# Hub.net
KiCad netlist of a schematic drawn in EAGLE
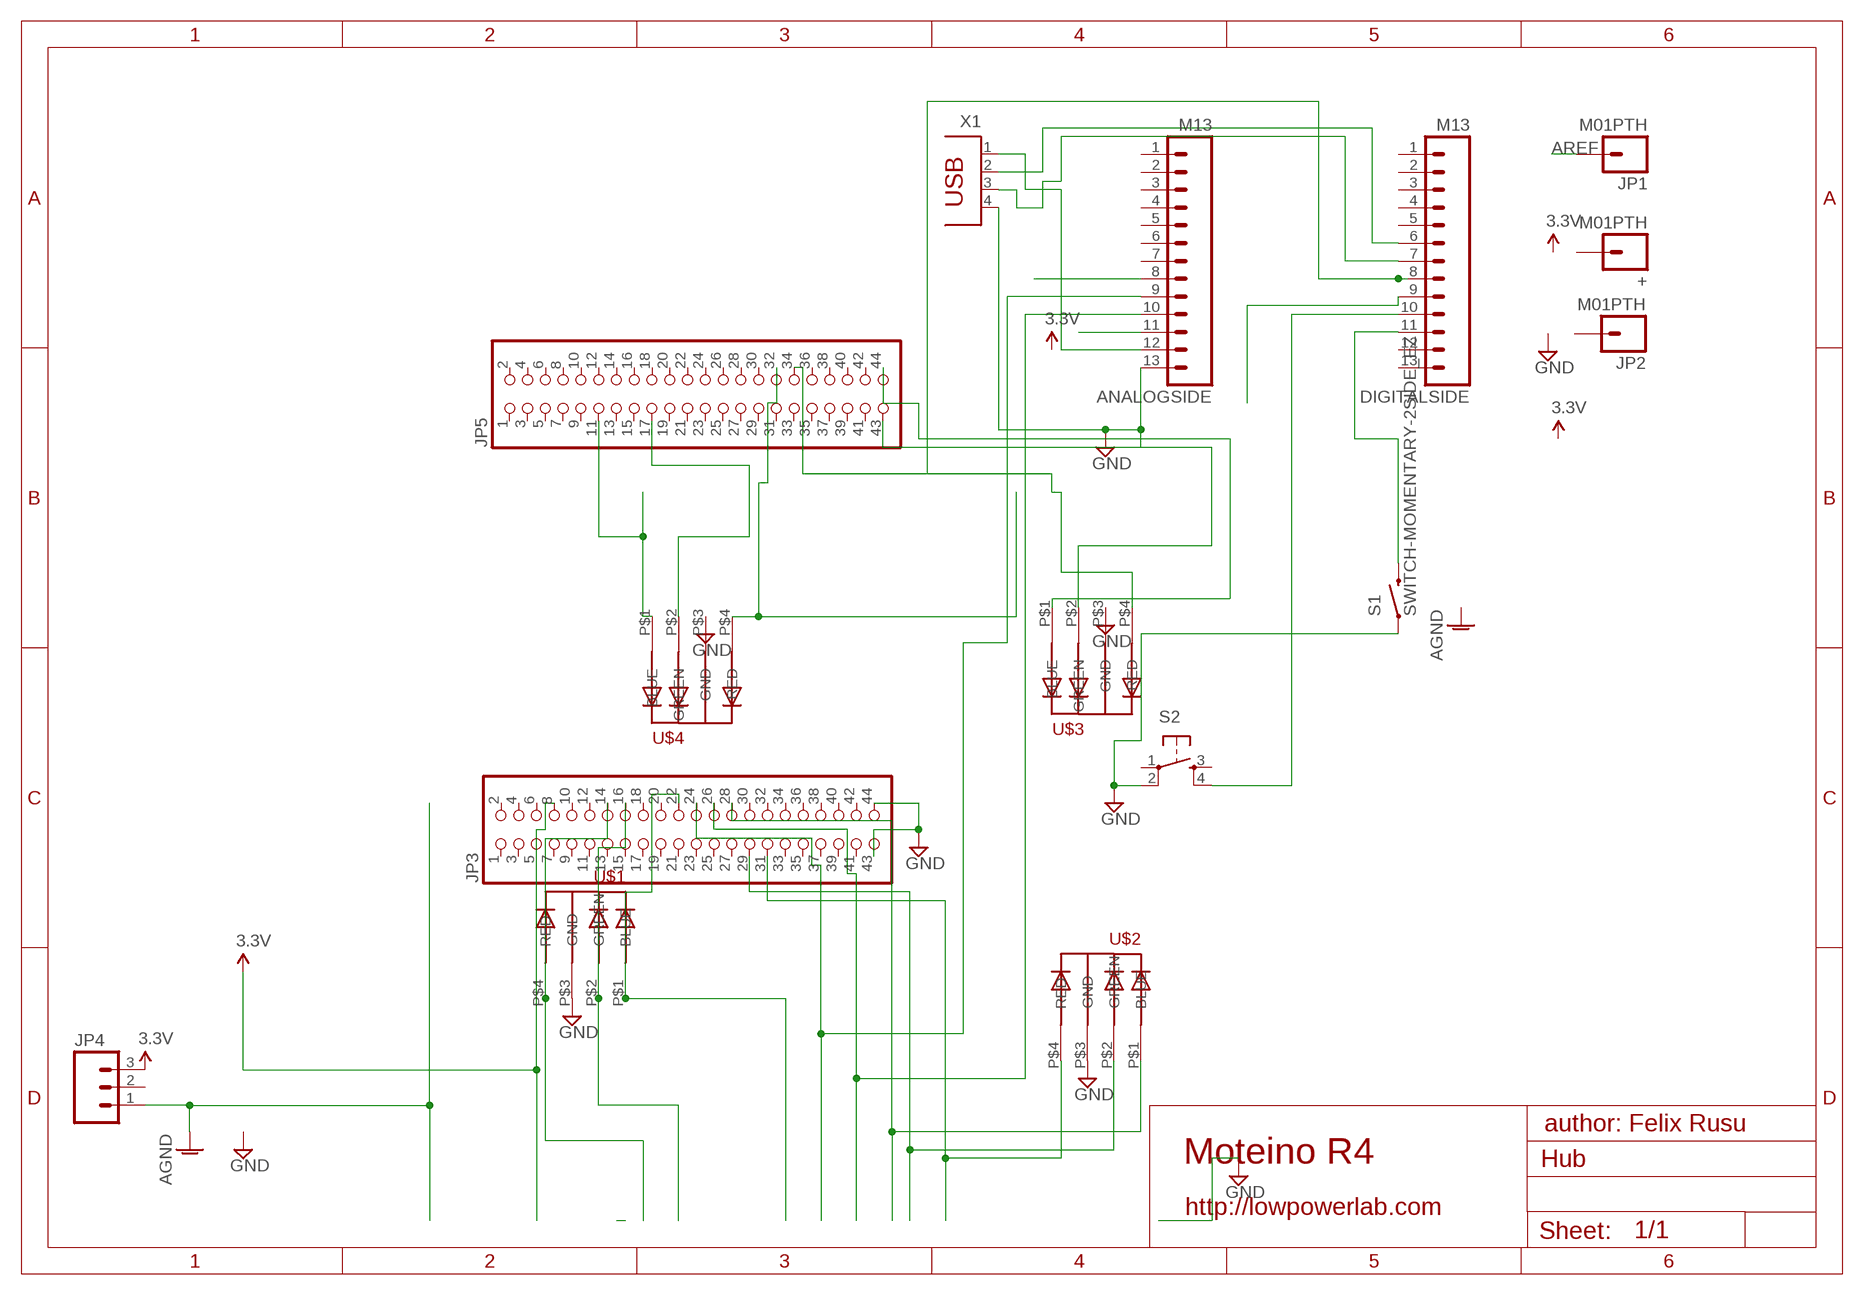
[diagram p0: schematic, sheet 1]

(export (version "E")
  (design (tool "Eeschema 10.0.6"))
  (components
    (comp (ref "+")
      (value "M01PTH")
      (footprint "eagle-import:1X01")
      (libsource (lib "eagle-import") (part "M01PTH"))
    )
    (comp (ref "ANALOGSIDE")
      (value "M13")
      (footprint "eagle-import:1X13")
      (libsource (lib "eagle-import") (part "M13"))
    )
    (comp (ref "DIGITALSIDE")
      (value "M13")
      (footprint "eagle-import:1X13")
      (libsource (lib "eagle-import") (part "M13"))
    )
    (comp (ref "JP1")
      (value "M01PTH")
      (footprint "eagle-import:1X01")
      (libsource (lib "eagle-import") (part "M01PTH"))
    )
    (comp (ref "JP2")
      (value "M01PTH")
      (footprint "eagle-import:1X01")
      (libsource (lib "eagle-import") (part "M01PTH"))
    )
    (comp (ref "JP3")
      (value "PINHD-2X22")
      (footprint "eagle-import:2X22")
      (libsource (lib "eagle-import") (part "PINHD-2X22"))
    )
    (comp (ref "JP4")
      (value "M03PTH")
      (footprint "eagle-import:1X03")
      (libsource (lib "eagle-import") (part "M03PTH"))
    )
    (comp (ref "JP5")
      (value "PINHD-2X22")
      (footprint "eagle-import:2X22")
      (libsource (lib "eagle-import") (part "PINHD-2X22"))
    )
    (comp (ref "S1")
      (value "SWITCH-MOMENTARY-2SIDE_EZ")
      (footprint "eagle-import:TACTILE-PTH-SIDEEZ")
      (libsource (lib "eagle-import") (part "SWITCH-MOMENTARY-2SIDE_EZ"))
    )
    (comp (ref "S2")
      (value "TAC_SWITCHPTH")
      (footprint "eagle-import:TACTILE-PTH")
      (libsource (lib "eagle-import") (part "TAC_SWITCHPTH"))
    )
    (comp (ref "U$1")
      (value "5MMRGBLED")
      (footprint "eagle-import:LED5MMRGB")
      (libsource (lib "eagle-import") (part "5MMRGBLED"))
    )
    (comp (ref "U$2")
      (value "5MMRGBLED")
      (footprint "eagle-import:LED5MMRGB")
      (libsource (lib "eagle-import") (part "5MMRGBLED"))
    )
    (comp (ref "U$3")
      (value "5MMRGBLED")
      (footprint "eagle-import:LED5MMRGB")
      (libsource (lib "eagle-import") (part "5MMRGBLED"))
    )
    (comp (ref "U$4")
      (value "5MMRGBLED")
      (footprint "eagle-import:LED5MMRGB")
      (libsource (lib "eagle-import") (part "5MMRGBLED"))
    )
    (comp (ref "X1")
      (value "PN87520")
      (footprint "eagle-import:PN87520")
      (libsource (lib "eagle-import") (part "PN87520"))
    )
  )
  (nets
    (net (code "1") (name "/AREF") (class "Default")
      (node (ref "JP1") (pin "1") (pinfunction "1_1") (pintype "passive"))
    )
    (net (code "2") (name "3.3V") (class "Default")
      (node (ref "JP3") (pin "8") (pinfunction "8_8") (pintype "passive"))
      (node (ref "JP4") (pin "3") (pinfunction "3_3") (pintype "passive"))
    )
    (net (code "3") (name "AGND") (class "Default")
      (node (ref "JP4") (pin "1") (pinfunction "1_1") (pintype "passive"))
    )
    (net (code "4") (name "GND") (class "Default")
      (node (ref "ANALOGSIDE") (pin "13") (pinfunction "13_13") (pintype "passive"))
      (node (ref "JP3") (pin "43") (pinfunction "43_43") (pintype "passive"))
      (node (ref "JP3") (pin "44") (pinfunction "44_44") (pintype "passive"))
      (node (ref "S1") (pin "1") (pinfunction "1_1") (pintype "passive"))
      (node (ref "S2") (pin "2") (pinfunction "2_2") (pintype "passive"))
      (node (ref "U$1") (pin "P$3") (pinfunction "GND_P$3") (pintype "bidirectional"))
      (node (ref "U$2") (pin "P$3") (pinfunction "GND_P$3") (pintype "bidirectional"))
      (node (ref "U$3") (pin "P$3") (pinfunction "GND_P$3") (pintype "bidirectional"))
      (node (ref "U$4") (pin "P$3") (pinfunction "GND_P$3") (pintype "bidirectional"))
      (node (ref "X1") (pin "4") (pinfunction "4_4") (pintype "passive"))
    )
    (net (code "5") (name "Net-(ANALOGSIDE-Pad9)") (class "Default")
      (node (ref "ANALOGSIDE") (pin "9") (pinfunction "9_9") (pintype "passive"))
      (node (ref "JP3") (pin "24") (pinfunction "24_24") (pintype "passive"))
    )
    (net (code "6") (name "Net-(ANALOGSIDE-Pad10)") (class "Default")
      (node (ref "ANALOGSIDE") (pin "10") (pinfunction "10_10") (pintype "passive"))
      (node (ref "JP3") (pin "26") (pinfunction "26_26") (pintype "passive"))
    )
    (net (code "7") (name "Net-(ANALOGSIDE-Pad12)") (class "Default")
      (node (ref "ANALOGSIDE") (pin "12") (pinfunction "12_12") (pintype "passive"))
      (node (ref "X1") (pin "1") (pinfunction "1_1") (pintype "passive"))
    )
    (net (code "8") (name "Net-(DIGITALSIDE-Pad6)") (class "Default")
      (node (ref "DIGITALSIDE") (pin "6") (pinfunction "6_6") (pintype "passive"))
      (node (ref "X1") (pin "2") (pinfunction "2_2") (pintype "passive"))
    )
    (net (code "9") (name "Net-(DIGITALSIDE-Pad7)") (class "Default")
      (node (ref "DIGITALSIDE") (pin "7") (pinfunction "7_7") (pintype "passive"))
      (node (ref "X1") (pin "3") (pinfunction "3_3") (pintype "passive"))
    )
    (net (code "10") (name "Net-(DIGITALSIDE-Pad10)") (class "Default")
      (node (ref "DIGITALSIDE") (pin "10") (pinfunction "10_10") (pintype "passive"))
      (node (ref "S2") (pin "4") (pinfunction "4_4") (pintype "passive"))
    )
    (net (code "11") (name "Net-(DIGITALSIDE-Pad11)") (class "Default")
      (node (ref "DIGITALSIDE") (pin "11") (pinfunction "11_11") (pintype "passive"))
      (node (ref "S1") (pin "2") (pinfunction "2_2") (pintype "passive"))
    )
    (net (code "12") (name "Net-(U$1-BLUE)") (class "Default")
      (node (ref "JP3") (pin "22") (pinfunction "22_22") (pintype "passive"))
      (node (ref "U$1") (pin "P$1") (pinfunction "BLUE_P$1") (pintype "bidirectional"))
    )
    (net (code "13") (name "Net-(U$1-GREEN)") (class "Default")
      (node (ref "JP3") (pin "16") (pinfunction "16_16") (pintype "passive"))
      (node (ref "U$1") (pin "P$2") (pinfunction "GREEN_P$2") (pintype "bidirectional"))
    )
    (net (code "14") (name "Net-(U$1-RED)") (class "Default")
      (node (ref "JP3") (pin "14") (pinfunction "14_14") (pintype "passive"))
      (node (ref "U$1") (pin "P$4") (pinfunction "RED_P$4") (pintype "bidirectional"))
    )
    (net (code "15") (name "Net-(U$2-BLUE)") (class "Default")
      (node (ref "JP3") (pin "28") (pinfunction "28_28") (pintype "passive"))
      (node (ref "U$2") (pin "P$1") (pinfunction "BLUE_P$1") (pintype "bidirectional"))
    )
    (net (code "16") (name "Net-(U$2-GREEN)") (class "Default")
      (node (ref "JP3") (pin "29") (pinfunction "29_29") (pintype "passive"))
      (node (ref "U$2") (pin "P$2") (pinfunction "GREEN_P$2") (pintype "bidirectional"))
    )
    (net (code "17") (name "Net-(U$2-RED)") (class "Default")
      (node (ref "JP3") (pin "31") (pinfunction "31_31") (pintype "passive"))
      (node (ref "U$2") (pin "P$4") (pinfunction "RED_P$4") (pintype "bidirectional"))
    )
    (net (code "18") (name "Net-(U$3-BLUE)") (class "Default")
      (node (ref "JP5") (pin "44") (pinfunction "44_44") (pintype "passive"))
      (node (ref "U$3") (pin "P$1") (pinfunction "BLUE_P$1") (pintype "bidirectional"))
    )
    (net (code "19") (name "Net-(U$3-GREEN)") (class "Default")
      (node (ref "JP5") (pin "43") (pinfunction "43_43") (pintype "passive"))
      (node (ref "U$3") (pin "P$2") (pinfunction "GREEN_P$2") (pintype "bidirectional"))
    )
    (net (code "20") (name "Net-(U$3-RED)") (class "Default")
      (node (ref "JP5") (pin "34") (pinfunction "34_34") (pintype "passive"))
      (node (ref "U$3") (pin "P$4") (pinfunction "RED_P$4") (pintype "bidirectional"))
    )
    (net (code "21") (name "Net-(U$4-BLUE)") (class "Default")
      (node (ref "JP5") (pin "11") (pinfunction "11_11") (pintype "passive"))
      (node (ref "U$4") (pin "P$1") (pinfunction "BLUE_P$1") (pintype "bidirectional"))
    )
    (net (code "22") (name "Net-(U$4-GREEN)") (class "Default")
      (node (ref "JP5") (pin "17") (pinfunction "17_17") (pintype "passive"))
      (node (ref "U$4") (pin "P$2") (pinfunction "GREEN_P$2") (pintype "bidirectional"))
    )
    (net (code "23") (name "Net-(U$4-RED)") (class "Default")
      (node (ref "JP5") (pin "32") (pinfunction "32_32") (pintype "passive"))
      (node (ref "U$4") (pin "P$4") (pinfunction "RED_P$4") (pintype "bidirectional"))
    )
    (net (code "24") (name "unconnected-(+-Pad1)") (class "Default")
      (node (ref "+") (pin "1") (pinfunction "1_1") (pintype "passive"))
    )
    (net (code "25") (name "unconnected-(ANALOGSIDE-Pad1)") (class "Default")
      (node (ref "ANALOGSIDE") (pin "1") (pinfunction "1_1") (pintype "passive"))
    )
    (net (code "26") (name "unconnected-(ANALOGSIDE-Pad2)") (class "Default")
      (node (ref "ANALOGSIDE") (pin "2") (pinfunction "2_2") (pintype "passive"))
    )
    (net (code "27") (name "unconnected-(ANALOGSIDE-Pad3)") (class "Default")
      (node (ref "ANALOGSIDE") (pin "3") (pinfunction "3_3") (pintype "passive"))
    )
    (net (code "28") (name "unconnected-(ANALOGSIDE-Pad4)") (class "Default")
      (node (ref "ANALOGSIDE") (pin "4") (pinfunction "4_4") (pintype "passive"))
    )
    (net (code "29") (name "unconnected-(ANALOGSIDE-Pad5)") (class "Default")
      (node (ref "ANALOGSIDE") (pin "5") (pinfunction "5_5") (pintype "passive"))
    )
    (net (code "30") (name "unconnected-(ANALOGSIDE-Pad6)") (class "Default")
      (node (ref "ANALOGSIDE") (pin "6") (pinfunction "6_6") (pintype "passive"))
    )
    (net (code "31") (name "unconnected-(ANALOGSIDE-Pad7)") (class "Default")
      (node (ref "ANALOGSIDE") (pin "7") (pinfunction "7_7") (pintype "passive"))
    )
    (net (code "32") (name "unconnected-(ANALOGSIDE-Pad8)") (class "Default")
      (node (ref "ANALOGSIDE") (pin "8") (pinfunction "8_8") (pintype "passive"))
    )
    (net (code "33") (name "unconnected-(ANALOGSIDE-Pad11)") (class "Default")
      (node (ref "ANALOGSIDE") (pin "11") (pinfunction "11_11") (pintype "passive"))
    )
    (net (code "34") (name "unconnected-(DIGITALSIDE-Pad1)") (class "Default")
      (node (ref "DIGITALSIDE") (pin "1") (pinfunction "1_1") (pintype "passive"))
    )
    (net (code "35") (name "unconnected-(DIGITALSIDE-Pad2)") (class "Default")
      (node (ref "DIGITALSIDE") (pin "2") (pinfunction "2_2") (pintype "passive"))
    )
    (net (code "36") (name "unconnected-(DIGITALSIDE-Pad3)") (class "Default")
      (node (ref "DIGITALSIDE") (pin "3") (pinfunction "3_3") (pintype "passive"))
    )
    (net (code "37") (name "unconnected-(DIGITALSIDE-Pad4)") (class "Default")
      (node (ref "DIGITALSIDE") (pin "4") (pinfunction "4_4") (pintype "passive"))
    )
    (net (code "38") (name "unconnected-(DIGITALSIDE-Pad5)") (class "Default")
      (node (ref "DIGITALSIDE") (pin "5") (pinfunction "5_5") (pintype "passive"))
    )
    (net (code "39") (name "unconnected-(DIGITALSIDE-Pad8)") (class "Default")
      (node (ref "DIGITALSIDE") (pin "8") (pinfunction "8_8") (pintype "passive"))
    )
    (net (code "40") (name "unconnected-(DIGITALSIDE-Pad9)") (class "Default")
      (node (ref "DIGITALSIDE") (pin "9") (pinfunction "9_9") (pintype "passive"))
    )
    (net (code "41") (name "unconnected-(DIGITALSIDE-Pad12)") (class "Default")
      (node (ref "DIGITALSIDE") (pin "12") (pinfunction "12_12") (pintype "passive"))
    )
    (net (code "42") (name "unconnected-(DIGITALSIDE-Pad13)") (class "Default")
      (node (ref "DIGITALSIDE") (pin "13") (pinfunction "13_13") (pintype "passive"))
    )
    (net (code "43") (name "unconnected-(JP2-Pad1)") (class "Default")
      (node (ref "JP2") (pin "1") (pinfunction "1_1") (pintype "passive"))
    )
    (net (code "44") (name "unconnected-(JP3-Pad1)") (class "Default")
      (node (ref "JP3") (pin "1") (pinfunction "1_1") (pintype "passive"))
    )
    (net (code "45") (name "unconnected-(JP3-Pad2)") (class "Default")
      (node (ref "JP3") (pin "2") (pinfunction "2_2") (pintype "passive"))
    )
    (net (code "46") (name "unconnected-(JP3-Pad3)") (class "Default")
      (node (ref "JP3") (pin "3") (pinfunction "3_3") (pintype "passive"))
    )
    (net (code "47") (name "unconnected-(JP3-Pad4)") (class "Default")
      (node (ref "JP3") (pin "4") (pinfunction "4_4") (pintype "passive"))
    )
    (net (code "48") (name "unconnected-(JP3-Pad5)") (class "Default")
      (node (ref "JP3") (pin "5") (pinfunction "5_5") (pintype "passive"))
    )
    (net (code "49") (name "unconnected-(JP3-Pad6)") (class "Default")
      (node (ref "JP3") (pin "6") (pinfunction "6_6") (pintype "passive"))
    )
    (net (code "50") (name "unconnected-(JP3-Pad7)") (class "Default")
      (node (ref "JP3") (pin "7") (pinfunction "7_7") (pintype "passive"))
    )
    (net (code "51") (name "unconnected-(JP3-Pad9)") (class "Default")
      (node (ref "JP3") (pin "9") (pinfunction "9_9") (pintype "passive"))
    )
    (net (code "52") (name "unconnected-(JP3-Pad10)") (class "Default")
      (node (ref "JP3") (pin "10") (pinfunction "10_10") (pintype "passive"))
    )
    (net (code "53") (name "unconnected-(JP3-Pad11)") (class "Default")
      (node (ref "JP3") (pin "11") (pinfunction "11_11") (pintype "passive"))
    )
    (net (code "54") (name "unconnected-(JP3-Pad12)") (class "Default")
      (node (ref "JP3") (pin "12") (pinfunction "12_12") (pintype "passive"))
    )
    (net (code "55") (name "unconnected-(JP3-Pad13)") (class "Default")
      (node (ref "JP3") (pin "13") (pinfunction "13_13") (pintype "passive"))
    )
    (net (code "56") (name "unconnected-(JP3-Pad15)") (class "Default")
      (node (ref "JP3") (pin "15") (pinfunction "15_15") (pintype "passive"))
    )
    (net (code "57") (name "unconnected-(JP3-Pad17)") (class "Default")
      (node (ref "JP3") (pin "17") (pinfunction "17_17") (pintype "passive"))
    )
    (net (code "58") (name "unconnected-(JP3-Pad18)") (class "Default")
      (node (ref "JP3") (pin "18") (pinfunction "18_18") (pintype "passive"))
    )
    (net (code "59") (name "unconnected-(JP3-Pad19)") (class "Default")
      (node (ref "JP3") (pin "19") (pinfunction "19_19") (pintype "passive"))
    )
    (net (code "60") (name "unconnected-(JP3-Pad20)") (class "Default")
      (node (ref "JP3") (pin "20") (pinfunction "20_20") (pintype "passive"))
    )
    (net (code "61") (name "unconnected-(JP3-Pad21)") (class "Default")
      (node (ref "JP3") (pin "21") (pinfunction "21_21") (pintype "passive"))
    )
    (net (code "62") (name "unconnected-(JP3-Pad23)") (class "Default")
      (node (ref "JP3") (pin "23") (pinfunction "23_23") (pintype "passive"))
    )
    (net (code "63") (name "unconnected-(JP3-Pad25)") (class "Default")
      (node (ref "JP3") (pin "25") (pinfunction "25_25") (pintype "passive"))
    )
    (net (code "64") (name "unconnected-(JP3-Pad27)") (class "Default")
      (node (ref "JP3") (pin "27") (pinfunction "27_27") (pintype "passive"))
    )
    (net (code "65") (name "unconnected-(JP3-Pad30)") (class "Default")
      (node (ref "JP3") (pin "30") (pinfunction "30_30") (pintype "passive"))
    )
    (net (code "66") (name "unconnected-(JP3-Pad32)") (class "Default")
      (node (ref "JP3") (pin "32") (pinfunction "32_32") (pintype "passive"))
    )
    (net (code "67") (name "unconnected-(JP3-Pad33)") (class "Default")
      (node (ref "JP3") (pin "33") (pinfunction "33_33") (pintype "passive"))
    )
    (net (code "68") (name "unconnected-(JP3-Pad34)") (class "Default")
      (node (ref "JP3") (pin "34") (pinfunction "34_34") (pintype "passive"))
    )
    (net (code "69") (name "unconnected-(JP3-Pad35)") (class "Default")
      (node (ref "JP3") (pin "35") (pinfunction "35_35") (pintype "passive"))
    )
    (net (code "70") (name "unconnected-(JP3-Pad36)") (class "Default")
      (node (ref "JP3") (pin "36") (pinfunction "36_36") (pintype "passive"))
    )
    (net (code "71") (name "unconnected-(JP3-Pad37)") (class "Default")
      (node (ref "JP3") (pin "37") (pinfunction "37_37") (pintype "passive"))
    )
    (net (code "72") (name "unconnected-(JP3-Pad38)") (class "Default")
      (node (ref "JP3") (pin "38") (pinfunction "38_38") (pintype "passive"))
    )
    (net (code "73") (name "unconnected-(JP3-Pad39)") (class "Default")
      (node (ref "JP3") (pin "39") (pinfunction "39_39") (pintype "passive"))
    )
    (net (code "74") (name "unconnected-(JP3-Pad40)") (class "Default")
      (node (ref "JP3") (pin "40") (pinfunction "40_40") (pintype "passive"))
    )
    (net (code "75") (name "unconnected-(JP3-Pad41)") (class "Default")
      (node (ref "JP3") (pin "41") (pinfunction "41_41") (pintype "passive"))
    )
    (net (code "76") (name "unconnected-(JP3-Pad42)") (class "Default")
      (node (ref "JP3") (pin "42") (pinfunction "42_42") (pintype "passive"))
    )
    (net (code "77") (name "unconnected-(JP4-Pad2)") (class "Default")
      (node (ref "JP4") (pin "2") (pinfunction "2_2") (pintype "passive"))
    )
    (net (code "78") (name "unconnected-(JP5-Pad1)") (class "Default")
      (node (ref "JP5") (pin "1") (pinfunction "1_1") (pintype "passive"))
    )
    (net (code "79") (name "unconnected-(JP5-Pad2)") (class "Default")
      (node (ref "JP5") (pin "2") (pinfunction "2_2") (pintype "passive"))
    )
    (net (code "80") (name "unconnected-(JP5-Pad3)") (class "Default")
      (node (ref "JP5") (pin "3") (pinfunction "3_3") (pintype "passive"))
    )
    (net (code "81") (name "unconnected-(JP5-Pad4)") (class "Default")
      (node (ref "JP5") (pin "4") (pinfunction "4_4") (pintype "passive"))
    )
    (net (code "82") (name "unconnected-(JP5-Pad5)") (class "Default")
      (node (ref "JP5") (pin "5") (pinfunction "5_5") (pintype "passive"))
    )
    (net (code "83") (name "unconnected-(JP5-Pad6)") (class "Default")
      (node (ref "JP5") (pin "6") (pinfunction "6_6") (pintype "passive"))
    )
    (net (code "84") (name "unconnected-(JP5-Pad7)") (class "Default")
      (node (ref "JP5") (pin "7") (pinfunction "7_7") (pintype "passive"))
    )
    (net (code "85") (name "unconnected-(JP5-Pad8)") (class "Default")
      (node (ref "JP5") (pin "8") (pinfunction "8_8") (pintype "passive"))
    )
    (net (code "86") (name "unconnected-(JP5-Pad9)") (class "Default")
      (node (ref "JP5") (pin "9") (pinfunction "9_9") (pintype "passive"))
    )
    (net (code "87") (name "unconnected-(JP5-Pad10)") (class "Default")
      (node (ref "JP5") (pin "10") (pinfunction "10_10") (pintype "passive"))
    )
    (net (code "88") (name "unconnected-(JP5-Pad12)") (class "Default")
      (node (ref "JP5") (pin "12") (pinfunction "12_12") (pintype "passive"))
    )
    (net (code "89") (name "unconnected-(JP5-Pad13)") (class "Default")
      (node (ref "JP5") (pin "13") (pinfunction "13_13") (pintype "passive"))
    )
    (net (code "90") (name "unconnected-(JP5-Pad14)") (class "Default")
      (node (ref "JP5") (pin "14") (pinfunction "14_14") (pintype "passive"))
    )
    (net (code "91") (name "unconnected-(JP5-Pad15)") (class "Default")
      (node (ref "JP5") (pin "15") (pinfunction "15_15") (pintype "passive"))
    )
    (net (code "92") (name "unconnected-(JP5-Pad16)") (class "Default")
      (node (ref "JP5") (pin "16") (pinfunction "16_16") (pintype "passive"))
    )
    (net (code "93") (name "unconnected-(JP5-Pad18)") (class "Default")
      (node (ref "JP5") (pin "18") (pinfunction "18_18") (pintype "passive"))
    )
    (net (code "94") (name "unconnected-(JP5-Pad19)") (class "Default")
      (node (ref "JP5") (pin "19") (pinfunction "19_19") (pintype "passive"))
    )
    (net (code "95") (name "unconnected-(JP5-Pad20)") (class "Default")
      (node (ref "JP5") (pin "20") (pinfunction "20_20") (pintype "passive"))
    )
    (net (code "96") (name "unconnected-(JP5-Pad21)") (class "Default")
      (node (ref "JP5") (pin "21") (pinfunction "21_21") (pintype "passive"))
    )
    (net (code "97") (name "unconnected-(JP5-Pad22)") (class "Default")
      (node (ref "JP5") (pin "22") (pinfunction "22_22") (pintype "passive"))
    )
    (net (code "98") (name "unconnected-(JP5-Pad23)") (class "Default")
      (node (ref "JP5") (pin "23") (pinfunction "23_23") (pintype "passive"))
    )
    (net (code "99") (name "unconnected-(JP5-Pad24)") (class "Default")
      (node (ref "JP5") (pin "24") (pinfunction "24_24") (pintype "passive"))
    )
    (net (code "100") (name "unconnected-(JP5-Pad25)") (class "Default")
      (node (ref "JP5") (pin "25") (pinfunction "25_25") (pintype "passive"))
    )
    (net (code "101") (name "unconnected-(JP5-Pad26)") (class "Default")
      (node (ref "JP5") (pin "26") (pinfunction "26_26") (pintype "passive"))
    )
    (net (code "102") (name "unconnected-(JP5-Pad27)") (class "Default")
      (node (ref "JP5") (pin "27") (pinfunction "27_27") (pintype "passive"))
    )
    (net (code "103") (name "unconnected-(JP5-Pad28)") (class "Default")
      (node (ref "JP5") (pin "28") (pinfunction "28_28") (pintype "passive"))
    )
    (net (code "104") (name "unconnected-(JP5-Pad29)") (class "Default")
      (node (ref "JP5") (pin "29") (pinfunction "29_29") (pintype "passive"))
    )
    (net (code "105") (name "unconnected-(JP5-Pad30)") (class "Default")
      (node (ref "JP5") (pin "30") (pinfunction "30_30") (pintype "passive"))
    )
    (net (code "106") (name "unconnected-(JP5-Pad31)") (class "Default")
      (node (ref "JP5") (pin "31") (pinfunction "31_31") (pintype "passive"))
    )
    (net (code "107") (name "unconnected-(JP5-Pad33)") (class "Default")
      (node (ref "JP5") (pin "33") (pinfunction "33_33") (pintype "passive"))
    )
    (net (code "108") (name "unconnected-(JP5-Pad35)") (class "Default")
      (node (ref "JP5") (pin "35") (pinfunction "35_35") (pintype "passive"))
    )
    (net (code "109") (name "unconnected-(JP5-Pad36)") (class "Default")
      (node (ref "JP5") (pin "36") (pinfunction "36_36") (pintype "passive"))
    )
    (net (code "110") (name "unconnected-(JP5-Pad37)") (class "Default")
      (node (ref "JP5") (pin "37") (pinfunction "37_37") (pintype "passive"))
    )
    (net (code "111") (name "unconnected-(JP5-Pad38)") (class "Default")
      (node (ref "JP5") (pin "38") (pinfunction "38_38") (pintype "passive"))
    )
    (net (code "112") (name "unconnected-(JP5-Pad39)") (class "Default")
      (node (ref "JP5") (pin "39") (pinfunction "39_39") (pintype "passive"))
    )
    (net (code "113") (name "unconnected-(JP5-Pad40)") (class "Default")
      (node (ref "JP5") (pin "40") (pinfunction "40_40") (pintype "passive"))
    )
    (net (code "114") (name "unconnected-(JP5-Pad41)") (class "Default")
      (node (ref "JP5") (pin "41") (pinfunction "41_41") (pintype "passive"))
    )
    (net (code "115") (name "unconnected-(JP5-Pad42)") (class "Default")
      (node (ref "JP5") (pin "42") (pinfunction "42_42") (pintype "passive"))
    )
    (net (code "116") (name "unconnected-(S2-Pad1)") (class "Default")
      (node (ref "S2") (pin "1") (pinfunction "1_1") (pintype "passive"))
    )
    (net (code "117") (name "unconnected-(S2-Pad3)") (class "Default")
      (node (ref "S2") (pin "3") (pinfunction "3_3") (pintype "passive"))
    )
  )
)
